# NoiseSampleHold.net
KiCad netlist of a schematic drawn in EAGLE
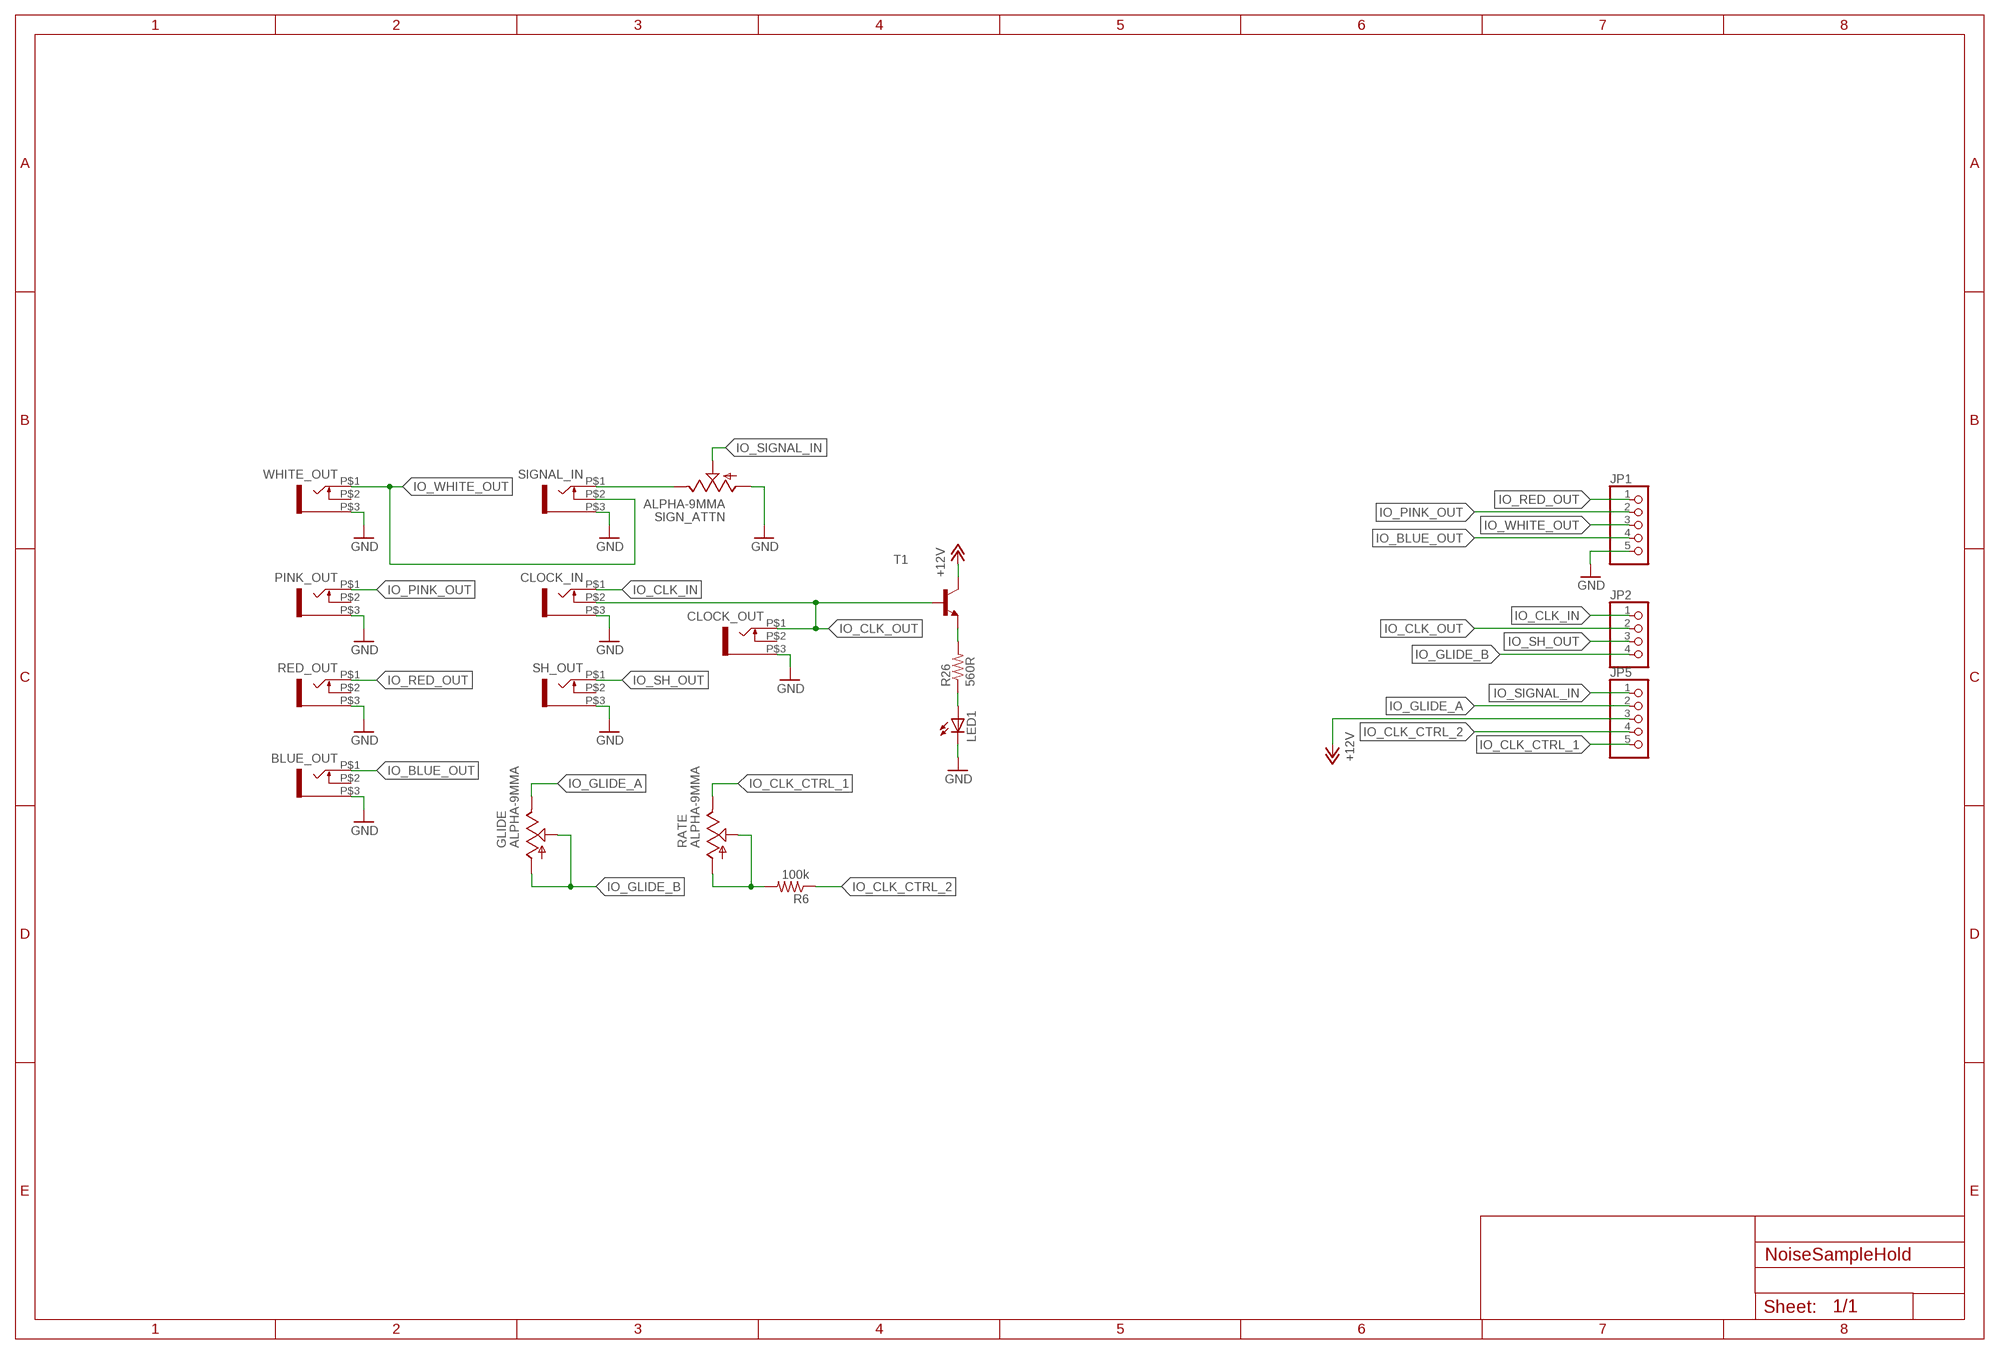
[diagram p0: schematic, sheet 1]

(export (version "E")
  (design (tool "Eeschema 10.0.6"))
  (components
    (comp (ref "BLUE_OUT")
      (value "WQP-PJ301M-12_JACK")
      (footprint "eagle-import:WQP-PJ301M-12_JACK")
      (libsource (lib "eagle-import") (part "WQP-PJ301M-12_JACK"))
    )
    (comp (ref "CLOCK_IN")
      (value "WQP-PJ301M-12_JACK")
      (footprint "eagle-import:WQP-PJ301M-12_JACK")
      (libsource (lib "eagle-import") (part "WQP-PJ301M-12_JACK"))
    )
    (comp (ref "CLOCK_OUT")
      (value "WQP-PJ301M-12_JACK")
      (footprint "eagle-import:WQP-PJ301M-12_JACK")
      (libsource (lib "eagle-import") (part "WQP-PJ301M-12_JACK"))
    )
    (comp (ref "GLIDE")
      (value "ALPHA-9MMA")
      (footprint "eagle-import:EVUF")
      (libsource (lib "eagle-import") (part "ALPHA-9MMA"))
    )
    (comp (ref "JP1")
      (value "PINHD-1X5")
      (footprint "eagle-import:1X05")
      (libsource (lib "eagle-import") (part "PINHD-1X5"))
    )
    (comp (ref "JP2")
      (value "PINHD-1X4")
      (footprint "eagle-import:1X04")
      (libsource (lib "eagle-import") (part "PINHD-1X4"))
    )
    (comp (ref "JP5")
      (value "PINHD-1X5")
      (footprint "eagle-import:1X05")
      (libsource (lib "eagle-import") (part "PINHD-1X5"))
    )
    (comp (ref "LED1")
      (value "LED3MM")
      (footprint "eagle-import:LED3MM")
      (libsource (lib "eagle-import") (part "LED3MM"))
    )
    (comp (ref "PINK_OUT")
      (value "WQP-PJ301M-12_JACK")
      (footprint "eagle-import:WQP-PJ301M-12_JACK")
      (libsource (lib "eagle-import") (part "WQP-PJ301M-12_JACK"))
    )
    (comp (ref "R6")
      (value "100k")
      (footprint "eagle-import:0204_7")
      (libsource (lib "eagle-import") (part "R-US_0204/7"))
    )
    (comp (ref "R26")
      (value "560R")
      (footprint "eagle-import:0204_7")
      (libsource (lib "eagle-import") (part "R-US_0204/7"))
    )
    (comp (ref "RATE")
      (value "ALPHA-9MMA")
      (footprint "eagle-import:EVUF")
      (libsource (lib "eagle-import") (part "ALPHA-9MMA"))
    )
    (comp (ref "RED_OUT")
      (value "WQP-PJ301M-12_JACK")
      (footprint "eagle-import:WQP-PJ301M-12_JACK")
      (libsource (lib "eagle-import") (part "WQP-PJ301M-12_JACK"))
    )
    (comp (ref "SH_OUT")
      (value "WQP-PJ301M-12_JACK")
      (footprint "eagle-import:WQP-PJ301M-12_JACK")
      (libsource (lib "eagle-import") (part "WQP-PJ301M-12_JACK"))
    )
    (comp (ref "SIGNAL_IN")
      (value "WQP-PJ301M-12_JACK")
      (footprint "eagle-import:WQP-PJ301M-12_JACK")
      (libsource (lib "eagle-import") (part "WQP-PJ301M-12_JACK"))
    )
    (comp (ref "SIGN_ATTN")
      (value "ALPHA-9MMA")
      (footprint "eagle-import:EVUF")
      (libsource (lib "eagle-import") (part "ALPHA-9MMA"))
    )
    (comp (ref "T1")
      (value "BC550-NPN-TO92-CBE")
      (footprint "eagle-import:TO92-CBE")
      (libsource (lib "eagle-import") (part "-NPN-TO92-CBEBC550"))
    )
    (comp (ref "WHITE_OUT")
      (value "WQP-PJ301M-12_JACK")
      (footprint "eagle-import:WQP-PJ301M-12_JACK")
      (libsource (lib "eagle-import") (part "WQP-PJ301M-12_JACK"))
    )
  )
  (nets
    (net (code "1") (name "+12V") (class "Default")
      (node (ref "JP5") (pin "3") (pinfunction "3_3") (pintype "passive"))
      (node (ref "T1") (pin "C") (pinfunction "C_C") (pintype "passive"))
    )
    (net (code "2") (name "GND") (class "Default")
      (node (ref "BLUE_OUT") (pin "P$3") (pinfunction "1_P$3") (pintype "passive"))
      (node (ref "CLOCK_IN") (pin "P$3") (pinfunction "1_P$3") (pintype "passive"))
      (node (ref "CLOCK_OUT") (pin "P$3") (pinfunction "1_P$3") (pintype "passive"))
      (node (ref "JP1") (pin "5") (pinfunction "5_5") (pintype "passive"))
      (node (ref "LED1") (pin "K") (pinfunction "C_K") (pintype "passive"))
      (node (ref "PINK_OUT") (pin "P$3") (pinfunction "1_P$3") (pintype "passive"))
      (node (ref "RED_OUT") (pin "P$3") (pinfunction "1_P$3") (pintype "passive"))
      (node (ref "SH_OUT") (pin "P$3") (pinfunction "1_P$3") (pintype "passive"))
      (node (ref "SIGNAL_IN") (pin "P$3") (pinfunction "1_P$3") (pintype "passive"))
      (node (ref "SIGN_ATTN") (pin "1") (pinfunction "A_1") (pintype "passive"))
      (node (ref "WHITE_OUT") (pin "P$3") (pinfunction "1_P$3") (pintype "passive"))
    )
    (net (code "3") (name "IO_BLUE_OUT") (class "Default")
      (node (ref "BLUE_OUT") (pin "P$1") (pinfunction "2_P$1") (pintype "passive"))
      (node (ref "JP1") (pin "4") (pinfunction "4_4") (pintype "passive"))
    )
    (net (code "4") (name "IO_CLK_CTRL_1") (class "Default")
      (node (ref "JP5") (pin "5") (pinfunction "5_5") (pintype "passive"))
      (node (ref "RATE") (pin "3") (pinfunction "E_3") (pintype "passive"))
    )
    (net (code "5") (name "IO_CLK_CTRL_2") (class "Default")
      (node (ref "JP5") (pin "4") (pinfunction "4_4") (pintype "passive"))
      (node (ref "R6") (pin "1") (pinfunction "1_1") (pintype "passive"))
    )
    (net (code "6") (name "IO_CLK_IN") (class "Default")
      (node (ref "CLOCK_IN") (pin "P$1") (pinfunction "2_P$1") (pintype "passive"))
      (node (ref "JP2") (pin "1") (pinfunction "1_1") (pintype "passive"))
    )
    (net (code "7") (name "IO_CLK_OUT") (class "Default")
      (node (ref "CLOCK_IN") (pin "P$2") (pinfunction "3_P$2") (pintype "passive"))
      (node (ref "CLOCK_OUT") (pin "P$1") (pinfunction "2_P$1") (pintype "passive"))
      (node (ref "JP2") (pin "2") (pinfunction "2_2") (pintype "passive"))
      (node (ref "T1") (pin "B") (pinfunction "B_B") (pintype "passive"))
    )
    (net (code "8") (name "IO_GLIDE_A") (class "Default")
      (node (ref "GLIDE") (pin "3") (pinfunction "E_3") (pintype "passive"))
      (node (ref "JP5") (pin "2") (pinfunction "2_2") (pintype "passive"))
    )
    (net (code "9") (name "IO_GLIDE_B") (class "Default")
      (node (ref "GLIDE") (pin "1") (pinfunction "A_1") (pintype "passive"))
      (node (ref "GLIDE") (pin "2") (pinfunction "S_2") (pintype "passive"))
      (node (ref "JP2") (pin "4") (pinfunction "4_4") (pintype "passive"))
    )
    (net (code "10") (name "IO_PINK_OUT") (class "Default")
      (node (ref "JP1") (pin "2") (pinfunction "2_2") (pintype "passive"))
      (node (ref "PINK_OUT") (pin "P$1") (pinfunction "2_P$1") (pintype "passive"))
    )
    (net (code "11") (name "IO_RED_OUT") (class "Default")
      (node (ref "JP1") (pin "1") (pinfunction "1_1") (pintype "passive"))
      (node (ref "RED_OUT") (pin "P$1") (pinfunction "2_P$1") (pintype "passive"))
    )
    (net (code "12") (name "IO_SH_OUT") (class "Default")
      (node (ref "JP2") (pin "3") (pinfunction "3_3") (pintype "passive"))
      (node (ref "SH_OUT") (pin "P$1") (pinfunction "2_P$1") (pintype "passive"))
    )
    (net (code "13") (name "IO_SIGNAL_IN") (class "Default")
      (node (ref "JP5") (pin "1") (pinfunction "1_1") (pintype "passive"))
      (node (ref "SIGN_ATTN") (pin "2") (pinfunction "S_2") (pintype "passive"))
    )
    (net (code "14") (name "IO_WHITE_OUT") (class "Default")
      (node (ref "JP1") (pin "3") (pinfunction "3_3") (pintype "passive"))
      (node (ref "SIGNAL_IN") (pin "P$2") (pinfunction "3_P$2") (pintype "passive"))
      (node (ref "WHITE_OUT") (pin "P$1") (pinfunction "2_P$1") (pintype "passive"))
    )
    (net (code "15") (name "Net-(LED1-PadA)") (class "Default")
      (node (ref "LED1") (pin "A") (pinfunction "A_A") (pintype "passive"))
      (node (ref "R26") (pin "1") (pinfunction "1_1") (pintype "passive"))
    )
    (net (code "16") (name "Net-(R26-Pad2)") (class "Default")
      (node (ref "R26") (pin "2") (pinfunction "2_2") (pintype "passive"))
      (node (ref "T1") (pin "E") (pinfunction "E_E") (pintype "passive"))
    )
    (net (code "17") (name "Net-(RATE-A)") (class "Default")
      (node (ref "R6") (pin "2") (pinfunction "2_2") (pintype "passive"))
      (node (ref "RATE") (pin "1") (pinfunction "A_1") (pintype "passive"))
      (node (ref "RATE") (pin "2") (pinfunction "S_2") (pintype "passive"))
    )
    (net (code "18") (name "Net-(SIGNAL_IN-2)") (class "Default")
      (node (ref "SIGNAL_IN") (pin "P$1") (pinfunction "2_P$1") (pintype "passive"))
      (node (ref "SIGN_ATTN") (pin "3") (pinfunction "E_3") (pintype "passive"))
    )
    (net (code "19") (name "unconnected-(BLUE_OUT-3-PadP$2)") (class "Default")
      (node (ref "BLUE_OUT") (pin "P$2") (pinfunction "3_P$2") (pintype "passive"))
    )
    (net (code "20") (name "unconnected-(CLOCK_OUT-3-PadP$2)") (class "Default")
      (node (ref "CLOCK_OUT") (pin "P$2") (pinfunction "3_P$2") (pintype "passive"))
    )
    (net (code "21") (name "unconnected-(PINK_OUT-3-PadP$2)") (class "Default")
      (node (ref "PINK_OUT") (pin "P$2") (pinfunction "3_P$2") (pintype "passive"))
    )
    (net (code "22") (name "unconnected-(RED_OUT-3-PadP$2)") (class "Default")
      (node (ref "RED_OUT") (pin "P$2") (pinfunction "3_P$2") (pintype "passive"))
    )
    (net (code "23") (name "unconnected-(SH_OUT-3-PadP$2)") (class "Default")
      (node (ref "SH_OUT") (pin "P$2") (pinfunction "3_P$2") (pintype "passive"))
    )
    (net (code "24") (name "unconnected-(WHITE_OUT-3-PadP$2)") (class "Default")
      (node (ref "WHITE_OUT") (pin "P$2") (pinfunction "3_P$2") (pintype "passive"))
    )
  )
)
